# STM32F103_coreboard_1.net
KiCad netlist of a schematic drawn in Altium Designer
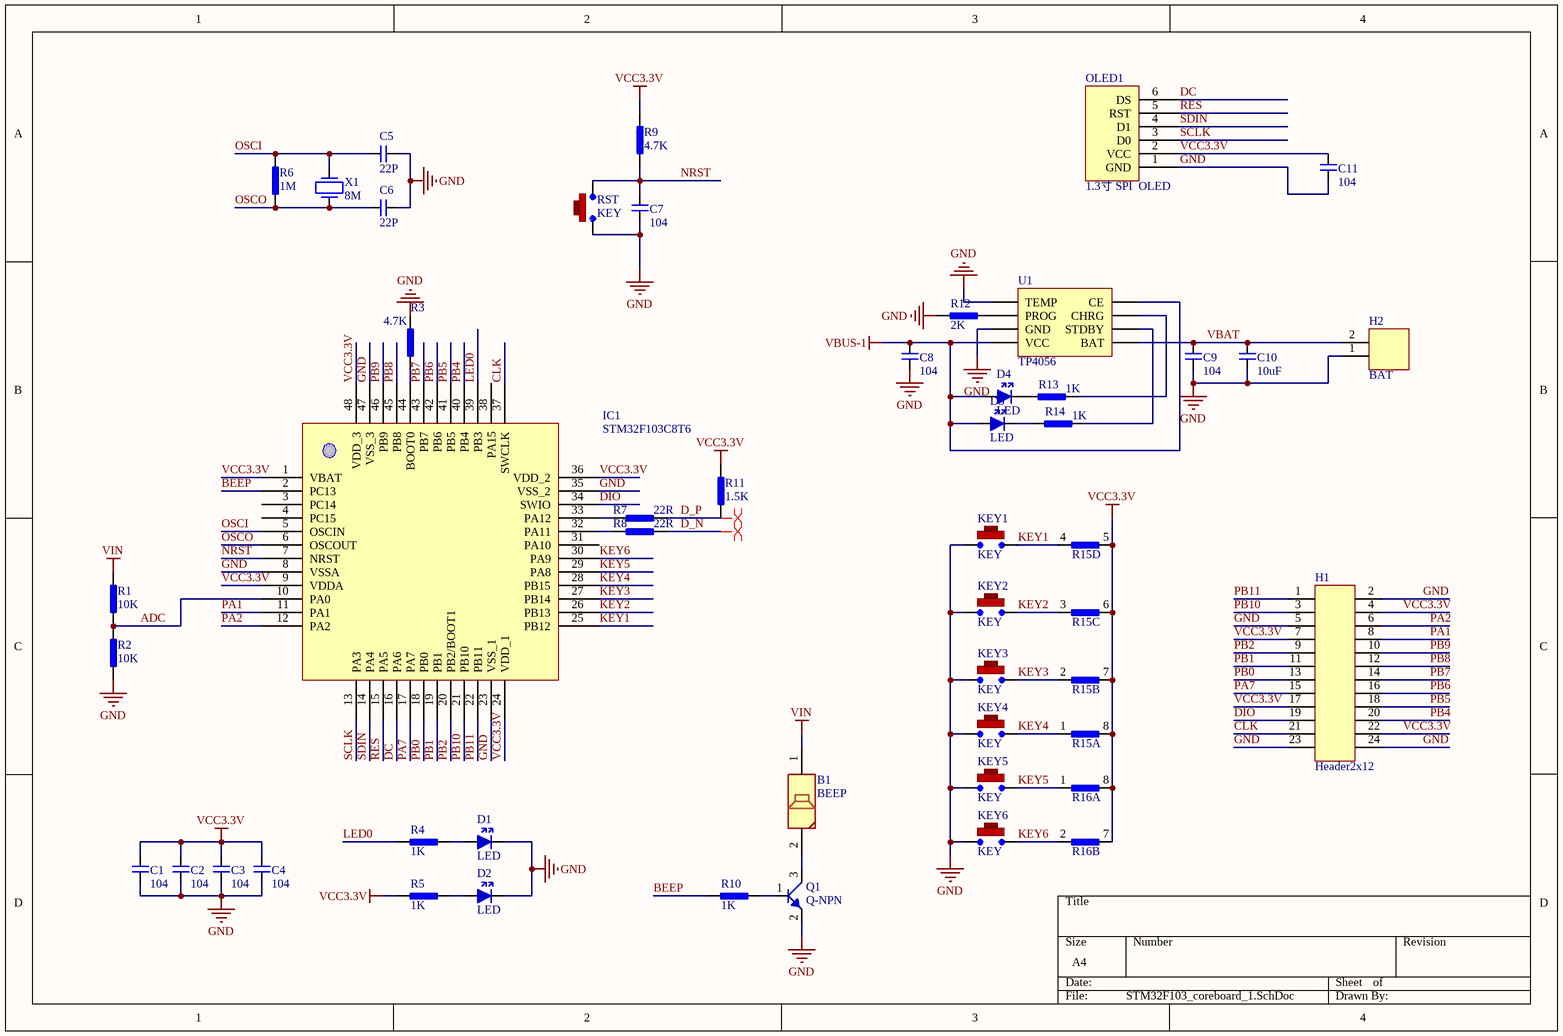
[diagram p0: STM32F103_coreboard_1.SchDoc]

(export (version "E")
  (design (tool "Eeschema 10.0.6"))
  (components
    (comp (ref "B1") (value "BEEP") (footprint "MLT-9650") (libsource (lib "SCH_Bacsic") (part "BEEP")))
    (comp (ref "C1")
      (value "104")
      (footprint "C0603")
      (description "Cap")
      (libsource (lib "SCH_Bacsic") (part "CAP"))
    )
    (comp (ref "C2")
      (value "104")
      (footprint "C0603")
      (description "Cap")
      (libsource (lib "SCH_Bacsic") (part "CAP"))
    )
    (comp (ref "C3")
      (value "104")
      (footprint "C0603")
      (description "Cap")
      (libsource (lib "SCH_Bacsic") (part "CAP"))
    )
    (comp (ref "C4")
      (value "104")
      (footprint "C0603")
      (description "Cap")
      (libsource (lib "SCH_Bacsic") (part "CAP"))
    )
    (comp (ref "C5")
      (value "22P")
      (footprint "C0603")
      (description "Cap")
      (libsource (lib "SCH_Bacsic") (part "CAP"))
    )
    (comp (ref "C6")
      (value "22P")
      (footprint "C0603")
      (description "Cap")
      (libsource (lib "SCH_Bacsic") (part "CAP"))
    )
    (comp (ref "C7")
      (value "104")
      (footprint "C0603")
      (description "Cap")
      (libsource (lib "SCH_Bacsic") (part "CAP"))
    )
    (comp (ref "C8")
      (value "104")
      (footprint "C0603")
      (description "Cap")
      (libsource (lib "SCH_Bacsic") (part "CAP"))
    )
    (comp (ref "C9")
      (value "104")
      (footprint "C0603")
      (description "Cap")
      (libsource (lib "SCH_Bacsic") (part "CAP"))
    )
    (comp (ref "C10")
      (value "10uF")
      (footprint "C0603")
      (description "Cap")
      (libsource (lib "SCH_Bacsic") (part "CAP"))
    )
    (comp (ref "C11")
      (value "104")
      (footprint "C0603")
      (description "Cap")
      (libsource (lib "SCH_Bacsic") (part "CAP"))
    )
    (comp (ref "D1") (value "LED") (footprint "LED0603") (libsource (lib "SCH_Bacsic") (part "LED")))
    (comp (ref "D2") (value "LED") (footprint "LED0603") (libsource (lib "SCH_Bacsic") (part "LED")))
    (comp (ref "D3") (value "LED") (footprint "LED0603") (libsource (lib "SCH_Bacsic") (part "LED")))
    (comp (ref "D4") (value "LED") (footprint "LED0603") (libsource (lib "SCH_Bacsic") (part "LED")))
    (comp (ref "H1")
      (value "Header2x12")
      (footprint "HDR2X12_2.54_180H")
      (libsource (lib "SCH_Connector") (part "Header2x12"))
    )
    (comp (ref "H2") (value "BAT") (footprint "BATIN") (libsource (lib "SCH_Connector") (part "Header1x2")))
    (comp (ref "IC1")
      (value "STM32F103C8T6")
      (footprint "LQFP48")
      (libsource (lib "SCH_Integrated_Circuit") (part "STM32F103C8T6"))
    )
    (comp (ref "KEY1")
      (value "KEY")
      (footprint "KEY3X4X2.5")
      (libsource (lib "SCH_Switch_and_Key") (part "KEY"))
    )
    (comp (ref "KEY2")
      (value "KEY")
      (footprint "KEY3X4X2.5")
      (libsource (lib "SCH_Switch_and_Key") (part "KEY"))
    )
    (comp (ref "KEY3")
      (value "KEY")
      (footprint "KEY3X4X2.5")
      (libsource (lib "SCH_Switch_and_Key") (part "KEY"))
    )
    (comp (ref "KEY4")
      (value "KEY")
      (footprint "KEY3X4X2.5")
      (libsource (lib "SCH_Switch_and_Key") (part "KEY"))
    )
    (comp (ref "KEY5")
      (value "KEY")
      (footprint "KEY3X4X2.5")
      (libsource (lib "SCH_Switch_and_Key") (part "KEY"))
    )
    (comp (ref "KEY6")
      (value "KEY")
      (footprint "KEY3X4X2.5")
      (libsource (lib "SCH_Switch_and_Key") (part "KEY"))
    )
    (comp (ref "OLED1")
      (value "1.3寸 SPI  OLED")
      (footprint "OLED1.3INCH")
      (description "1.3寸 SPI  OLED 128x64 6线")
      (libsource (lib "SCH_Independent_Component") (part "1.3寸 SPI  OLED"))
    )
    (comp (ref "Q1") (value "Q-NPN") (footprint "SOT-23") (libsource (lib "SCH_Bacsic") (part "Q-NPN")))
    (comp (ref "R1") (value "10K") (footprint "R0603") (libsource (lib "SCH_Bacsic") (part "RES")))
    (comp (ref "R2") (value "10K") (footprint "R0603") (libsource (lib "SCH_Bacsic") (part "RES")))
    (comp (ref "R3") (value "4.7K") (footprint "R0603") (libsource (lib "SCH_Bacsic") (part "RES")))
    (comp (ref "R4") (value "1K") (footprint "R0603") (libsource (lib "") (part "RES_1")))
    (comp (ref "R5") (value "1K") (footprint "R0603") (libsource (lib "") (part "RES_1")))
    (comp (ref "R6") (value "1M") (footprint "R0603") (libsource (lib "SCH_Bacsic") (part "RES")))
    (comp (ref "R7") (value "22R") (footprint "R0603") (libsource (lib "") (part "RES_1")))
    (comp (ref "R8") (value "22R") (footprint "R0603") (libsource (lib "") (part "RES_1")))
    (comp (ref "R9") (value "4.7K") (footprint "R0603") (libsource (lib "SCH_Bacsic") (part "RES")))
    (comp (ref "R10") (value "1K") (footprint "R0603") (libsource (lib "") (part "RES_1")))
    (comp (ref "R11") (value "1.5K") (footprint "R0603") (libsource (lib "SCH_Bacsic") (part "RES")))
    (comp (ref "R12") (value "2K") (footprint "R0603") (libsource (lib "") (part "RES_1")))
    (comp (ref "R13") (value "1K") (footprint "R0603") (libsource (lib "") (part "RES_1")))
    (comp (ref "R14") (value "1K") (footprint "R0603") (libsource (lib "") (part "RES_1")))
    (comp (ref "R15")
      (value "Res Pack-4R")
      (footprint "8P4R-0603")
      (description "排阻")
      (fields (field (name "PUBLISHER") "Altium Limited"))
      (libsource (lib "SCH_Bacsic") (part "Res Pack-4R"))
    )
    (comp (ref "R16")
      (value "Res Pack-4R")
      (footprint "8P4R-0603")
      (description "排阻")
      (fields (field (name "PUBLISHER") "Altium Limited"))
      (libsource (lib "SCH_Bacsic") (part "Res Pack-4R"))
    )
    (comp (ref "RST") (value "KEY") (footprint "KEY3X4X2.5") (libsource (lib "") (part "KEY_1")))
    (comp (ref "U1") (value "TP4056") (footprint "SOP8") (libsource (lib "常用原理图库") (part "TP4056")))
    (comp (ref "X1") (value "8M") (footprint "XTAL-5032") (libsource (lib "SCH_Bacsic") (part "XTAL")))
  )
  (nets
    (net (code "1") (name "/ADC") (class "Default")
      (node (ref "IC1") (pin "10") (pinfunction "PA0_10") (pintype "passive"))
      (node (ref "R1") (pin "1") (pintype "passive"))
      (node (ref "R2") (pin "2") (pintype "passive"))
    )
    (net (code "2") (name "/BEEP") (class "Default")
      (node (ref "IC1") (pin "2") (pinfunction "PC13_2") (pintype "passive"))
      (node (ref "R10") (pin "1") (pintype "passive"))
    )
    (net (code "3") (name "/CLK") (class "Default")
      (node (ref "H1") (pin "21") (pinfunction "21_21") (pintype "passive"))
      (node (ref "IC1") (pin "37") (pinfunction "SWCLK_37") (pintype "passive"))
    )
    (net (code "4") (name "/DC") (class "Default")
      (node (ref "IC1") (pin "16") (pinfunction "PA6_16") (pintype "passive"))
      (node (ref "OLED1") (pin "6") (pinfunction "DS_6") (pintype "passive"))
    )
    (net (code "5") (name "/DIO") (class "Default")
      (node (ref "H1") (pin "19") (pintype "passive"))
      (node (ref "IC1") (pin "34") (pinfunction "SWIO_34") (pintype "passive"))
    )
    (net (code "6") (name "/D_N") (class "Default") (node (ref "R8") (pin "2") (pintype "passive")))
    (net (code "7") (name "/D_P") (class "Default")
      (node (ref "R11") (pin "1") (pintype "passive"))
      (node (ref "R7") (pin "2") (pintype "passive"))
    )
    (net (code "8") (name "/KEY1") (class "Default")
      (node (ref "IC1") (pin "25") (pinfunction "PB12_25") (pintype "passive"))
      (node (ref "KEY1") (pin "2") (pintype "passive"))
      (node (ref "R15") (pin "4") (pinfunction "4_4") (pintype "passive"))
    )
    (net (code "9") (name "/KEY2") (class "Default")
      (node (ref "IC1") (pin "26") (pinfunction "PB13_26") (pintype "passive"))
      (node (ref "KEY2") (pin "2") (pintype "passive"))
      (node (ref "R15") (pin "3") (pinfunction "3_3") (pintype "passive"))
    )
    (net (code "10") (name "/KEY3") (class "Default")
      (node (ref "IC1") (pin "27") (pinfunction "PB14_27") (pintype "passive"))
      (node (ref "KEY3") (pin "2") (pintype "passive"))
      (node (ref "R15") (pin "2") (pinfunction "2_2") (pintype "passive"))
    )
    (net (code "11") (name "/KEY4") (class "Default")
      (node (ref "IC1") (pin "28") (pinfunction "PB15_28") (pintype "passive"))
      (node (ref "KEY4") (pin "2") (pintype "passive"))
      (node (ref "R15") (pin "1") (pinfunction "1_1") (pintype "passive"))
    )
    (net (code "12") (name "/KEY5") (class "Default")
      (node (ref "IC1") (pin "29") (pinfunction "PA8_29") (pintype "passive"))
      (node (ref "KEY5") (pin "2") (pintype "passive"))
      (node (ref "R16") (pin "1") (pinfunction "1_1") (pintype "passive"))
    )
    (net (code "13") (name "/KEY6") (class "Default")
      (node (ref "IC1") (pin "30") (pinfunction "PA9_30") (pintype "passive"))
      (node (ref "KEY6") (pin "2") (pintype "passive"))
      (node (ref "R16") (pin "2") (pinfunction "2_2") (pintype "passive"))
    )
    (net (code "14") (name "/LED0") (class "Default")
      (node (ref "IC1") (pin "39") (pinfunction "PB3_39") (pintype "passive"))
      (node (ref "R4") (pin "1") (pintype "passive"))
    )
    (net (code "15") (name "/NRST") (class "Default")
      (node (ref "C7") (pin "2") (pintype "passive"))
      (node (ref "IC1") (pin "7") (pinfunction "NRST_7") (pintype "passive"))
      (node (ref "R9") (pin "1") (pintype "passive"))
      (node (ref "RST") (pin "2") (pintype "passive"))
    )
    (net (code "16") (name "/OSCI") (class "Default")
      (node (ref "C5") (pin "1") (pintype "passive"))
      (node (ref "IC1") (pin "5") (pinfunction "OSCIN_5") (pintype "passive"))
      (node (ref "R6") (pin "2") (pintype "passive"))
      (node (ref "X1") (pin "2") (pintype "passive"))
    )
    (net (code "17") (name "/OSCO") (class "Default")
      (node (ref "C6") (pin "1") (pintype "passive"))
      (node (ref "IC1") (pin "6") (pinfunction "OSCOUT_6") (pintype "passive"))
      (node (ref "R6") (pin "1") (pintype "passive"))
      (node (ref "X1") (pin "1") (pintype "passive"))
    )
    (net (code "18") (name "/PA1") (class "Default")
      (node (ref "H1") (pin "8") (pintype "passive"))
      (node (ref "IC1") (pin "11") (pinfunction "PA1_11") (pintype "passive"))
    )
    (net (code "19") (name "/PA2") (class "Default")
      (node (ref "H1") (pin "6") (pintype "passive"))
      (node (ref "IC1") (pin "12") (pinfunction "PA2_12") (pintype "passive"))
    )
    (net (code "20") (name "/PA7") (class "Default")
      (node (ref "H1") (pin "15") (pintype "passive"))
      (node (ref "IC1") (pin "17") (pinfunction "PA7_17") (pintype "passive"))
    )
    (net (code "21") (name "/PB0") (class "Default")
      (node (ref "H1") (pin "13") (pintype "passive"))
      (node (ref "IC1") (pin "18") (pinfunction "PB0_18") (pintype "passive"))
    )
    (net (code "22") (name "/PB1") (class "Default")
      (node (ref "H1") (pin "11") (pintype "passive"))
      (node (ref "IC1") (pin "19") (pinfunction "PB1_19") (pintype "passive"))
    )
    (net (code "23") (name "/PB2") (class "Default")
      (node (ref "H1") (pin "9") (pintype "passive"))
      (node (ref "IC1") (pin "20") (pinfunction "PB2/BOOT1_20") (pintype "passive"))
    )
    (net (code "24") (name "/PB4") (class "Default")
      (node (ref "H1") (pin "20") (pintype "passive"))
      (node (ref "IC1") (pin "40") (pinfunction "PB4_40") (pintype "passive"))
    )
    (net (code "25") (name "/PB5") (class "Default")
      (node (ref "H1") (pin "18") (pintype "passive"))
      (node (ref "IC1") (pin "41") (pinfunction "PB5_41") (pintype "passive"))
    )
    (net (code "26") (name "/PB6") (class "Default")
      (node (ref "H1") (pin "16") (pintype "passive"))
      (node (ref "IC1") (pin "42") (pinfunction "PB6_42") (pintype "passive"))
    )
    (net (code "27") (name "/PB7") (class "Default")
      (node (ref "H1") (pin "14") (pintype "passive"))
      (node (ref "IC1") (pin "43") (pinfunction "PB7_43") (pintype "passive"))
    )
    (net (code "28") (name "/PB8") (class "Default")
      (node (ref "H1") (pin "12") (pintype "passive"))
      (node (ref "IC1") (pin "45") (pinfunction "PB8_45") (pintype "passive"))
    )
    (net (code "29") (name "/PB9") (class "Default")
      (node (ref "H1") (pin "10") (pintype "passive"))
      (node (ref "IC1") (pin "46") (pinfunction "PB9_46") (pintype "passive"))
    )
    (net (code "30") (name "/PB10") (class "Default")
      (node (ref "H1") (pin "3") (pintype "passive"))
      (node (ref "IC1") (pin "21") (pinfunction "PB10_21") (pintype "passive"))
    )
    (net (code "31") (name "/PB11") (class "Default")
      (node (ref "H1") (pin "1") (pintype "passive"))
      (node (ref "IC1") (pin "22") (pinfunction "PB11_22") (pintype "passive"))
    )
    (net (code "32") (name "/RES") (class "Default")
      (node (ref "IC1") (pin "15") (pinfunction "PA5_15") (pintype "passive"))
      (node (ref "OLED1") (pin "5") (pinfunction "RST_5") (pintype "passive"))
    )
    (net (code "33") (name "/SCLK") (class "Default")
      (node (ref "IC1") (pin "13") (pinfunction "PA3_13") (pintype "passive"))
      (node (ref "OLED1") (pin "3") (pinfunction "D0_3") (pintype "passive"))
    )
    (net (code "34") (name "/SDIN") (class "Default")
      (node (ref "IC1") (pin "14") (pinfunction "PA4_14") (pintype "passive"))
      (node (ref "OLED1") (pin "4") (pinfunction "D1_4") (pintype "passive"))
    )
    (net (code "35") (name "/VBAT") (class "Default")
      (node (ref "C10") (pin "2") (pintype "passive"))
      (node (ref "C9") (pin "2") (pintype "passive"))
      (node (ref "H2") (pin "2") (pintype "passive"))
      (node (ref "U1") (pin "5") (pinfunction "BAT_5") (pintype "passive"))
    )
    (net (code "36") (name "GND") (class "Default")
      (node (ref "C1") (pin "1") (pintype "passive"))
      (node (ref "C10") (pin "1") (pintype "passive"))
      (node (ref "C11") (pin "1") (pintype "passive"))
      (node (ref "C2") (pin "1") (pintype "passive"))
      (node (ref "C3") (pin "1") (pintype "passive"))
      (node (ref "C4") (pin "1") (pintype "passive"))
      (node (ref "C5") (pin "2") (pintype "passive"))
      (node (ref "C6") (pin "2") (pintype "passive"))
      (node (ref "C7") (pin "1") (pintype "passive"))
      (node (ref "C8") (pin "1") (pintype "passive"))
      (node (ref "C9") (pin "1") (pintype "passive"))
      (node (ref "D1") (pin "2") (pintype "passive"))
      (node (ref "D2") (pin "2") (pintype "passive"))
      (node (ref "H1") (pin "2") (pintype "passive"))
      (node (ref "H1") (pin "23") (pinfunction "23_23") (pintype "passive"))
      (node (ref "H1") (pin "24") (pinfunction "24_24") (pintype "passive"))
      (node (ref "H1") (pin "5") (pintype "passive"))
      (node (ref "H2") (pin "1") (pintype "passive"))
      (node (ref "IC1") (pin "23") (pinfunction "VSS_1_23") (pintype "passive"))
      (node (ref "IC1") (pin "35") (pinfunction "VSS_2_35") (pintype "passive"))
      (node (ref "IC1") (pin "47") (pinfunction "VSS_3_47") (pintype "passive"))
      (node (ref "IC1") (pin "8") (pinfunction "VSSA_8") (pintype "passive"))
      (node (ref "KEY1") (pin "1") (pintype "passive"))
      (node (ref "KEY2") (pin "1") (pintype "passive"))
      (node (ref "KEY3") (pin "1") (pintype "passive"))
      (node (ref "KEY4") (pin "1") (pintype "passive"))
      (node (ref "KEY5") (pin "1") (pintype "passive"))
      (node (ref "KEY6") (pin "1") (pintype "passive"))
      (node (ref "OLED1") (pin "1") (pinfunction "GND_1") (pintype "passive"))
      (node (ref "Q1") (pin "2") (pinfunction "2_2") (pintype "passive"))
      (node (ref "R12") (pin "1") (pintype "passive"))
      (node (ref "R2") (pin "1") (pintype "passive"))
      (node (ref "R3") (pin "2") (pintype "passive"))
      (node (ref "RST") (pin "1") (pintype "passive"))
      (node (ref "U1") (pin "1") (pinfunction "TEMP_1") (pintype "passive"))
      (node (ref "U1") (pin "3") (pinfunction "GND_3") (pintype "passive"))
    )
    (net (code "37") (name "Net-(B1-Pad2)") (class "Default")
      (node (ref "B1") (pin "2") (pintype "passive"))
      (node (ref "Q1") (pin "3") (pinfunction "3_3") (pintype "passive"))
    )
    (net (code "38") (name "Net-(D1-Pad1)") (class "Default")
      (node (ref "D1") (pin "1") (pintype "passive"))
      (node (ref "R4") (pin "2") (pintype "passive"))
    )
    (net (code "39") (name "Net-(D2-Pad1)") (class "Default")
      (node (ref "D2") (pin "1") (pintype "passive"))
      (node (ref "R5") (pin "2") (pintype "passive"))
    )
    (net (code "40") (name "Net-(D3-Pad2)") (class "Default")
      (node (ref "D3") (pin "2") (pintype "passive"))
      (node (ref "R14") (pin "1") (pintype "passive"))
    )
    (net (code "41") (name "Net-(D4-Pad2)") (class "Default")
      (node (ref "D4") (pin "2") (pintype "passive"))
      (node (ref "R13") (pin "1") (pintype "passive"))
    )
    (net (code "42") (name "Net-(IC1-BOOT0)") (class "Default")
      (node (ref "IC1") (pin "44") (pinfunction "BOOT0_44") (pintype "passive"))
      (node (ref "R3") (pin "1") (pintype "passive"))
    )
    (net (code "43") (name "Net-(IC1-PA11)") (class "Default")
      (node (ref "IC1") (pin "32") (pinfunction "PA11_32") (pintype "passive"))
      (node (ref "R8") (pin "1") (pintype "passive"))
    )
    (net (code "44") (name "Net-(IC1-PA12)") (class "Default")
      (node (ref "IC1") (pin "33") (pinfunction "PA12_33") (pintype "passive"))
      (node (ref "R7") (pin "1") (pintype "passive"))
    )
    (net (code "45") (name "Net-(Q1-Pad1)") (class "Default")
      (node (ref "Q1") (pin "1") (pinfunction "1_1") (pintype "passive"))
      (node (ref "R10") (pin "2") (pintype "passive"))
    )
    (net (code "46") (name "Net-(U1-CHRG)") (class "Default")
      (node (ref "R13") (pin "2") (pintype "passive"))
      (node (ref "U1") (pin "7") (pinfunction "CHRG_7") (pintype "passive"))
    )
    (net (code "47") (name "Net-(U1-PROG)") (class "Default")
      (node (ref "R12") (pin "2") (pintype "passive"))
      (node (ref "U1") (pin "2") (pinfunction "PROG_2") (pintype "passive"))
    )
    (net (code "48") (name "Net-(U1-STDBY)") (class "Default")
      (node (ref "R14") (pin "2") (pintype "passive"))
      (node (ref "U1") (pin "6") (pinfunction "STDBY_6") (pintype "passive"))
    )
    (net (code "49") (name "VBUS-1") (class "Default")
      (node (ref "C8") (pin "2") (pintype "passive"))
      (node (ref "D3") (pin "1") (pintype "passive"))
      (node (ref "D4") (pin "1") (pintype "passive"))
      (node (ref "U1") (pin "4") (pinfunction "VCC_4") (pintype "passive"))
      (node (ref "U1") (pin "8") (pinfunction "CE_8") (pintype "passive"))
    )
    (net (code "50") (name "VCC3.3V") (class "Default")
      (node (ref "C1") (pin "2") (pintype "passive"))
      (node (ref "C11") (pin "2") (pintype "passive"))
      (node (ref "C2") (pin "2") (pintype "passive"))
      (node (ref "C3") (pin "2") (pintype "passive"))
      (node (ref "C4") (pin "2") (pintype "passive"))
      (node (ref "H1") (pin "17") (pintype "passive"))
      (node (ref "H1") (pin "22") (pinfunction "22_22") (pintype "passive"))
      (node (ref "H1") (pin "4") (pintype "passive"))
      (node (ref "H1") (pin "7") (pintype "passive"))
      (node (ref "IC1") (pin "1") (pinfunction "VBAT_1") (pintype "passive"))
      (node (ref "IC1") (pin "24") (pinfunction "VDD_1_24") (pintype "passive"))
      (node (ref "IC1") (pin "36") (pinfunction "VDD_2_36") (pintype "passive"))
      (node (ref "IC1") (pin "48") (pinfunction "VDD_3_48") (pintype "passive"))
      (node (ref "IC1") (pin "9") (pinfunction "VDDA_9") (pintype "passive"))
      (node (ref "OLED1") (pin "2") (pinfunction "VCC_2") (pintype "passive"))
      (node (ref "R11") (pin "2") (pintype "passive"))
      (node (ref "R15") (pin "5") (pinfunction "5_5") (pintype "passive"))
      (node (ref "R15") (pin "6") (pinfunction "6_6") (pintype "passive"))
      (node (ref "R15") (pin "7") (pinfunction "7_7") (pintype "passive"))
      (node (ref "R15") (pin "8") (pinfunction "8_8") (pintype "passive"))
      (node (ref "R16") (pin "7") (pinfunction "7_7") (pintype "passive"))
      (node (ref "R16") (pin "8") (pinfunction "8_8") (pintype "passive"))
      (node (ref "R5") (pin "1") (pintype "passive"))
      (node (ref "R9") (pin "2") (pintype "passive"))
    )
    (net (code "51") (name "VIN") (class "Default")
      (node (ref "B1") (pin "1") (pintype "passive"))
      (node (ref "R1") (pin "2") (pintype "passive"))
    )
    (net (code "52") (name "unconnected-(IC1-PA10-Pad31)") (class "Default")
      (node (ref "IC1") (pin "31") (pinfunction "PA10_31") (pintype "passive"))
    )
    (net (code "53") (name "unconnected-(IC1-PA15-Pad38)") (class "Default")
      (node (ref "IC1") (pin "38") (pinfunction "PA15_38") (pintype "passive"))
    )
    (net (code "54") (name "unconnected-(IC1-PC14-Pad3)") (class "Default")
      (node (ref "IC1") (pin "3") (pinfunction "PC14_3") (pintype "passive"))
    )
    (net (code "55") (name "unconnected-(IC1-PC15-Pad4)") (class "Default")
      (node (ref "IC1") (pin "4") (pinfunction "PC15_4") (pintype "passive"))
    )
  )
)
